# Grove_-_Laser_PM2_5_Sensor_HM3301.net
KiCad netlist of a schematic drawn in EAGLE
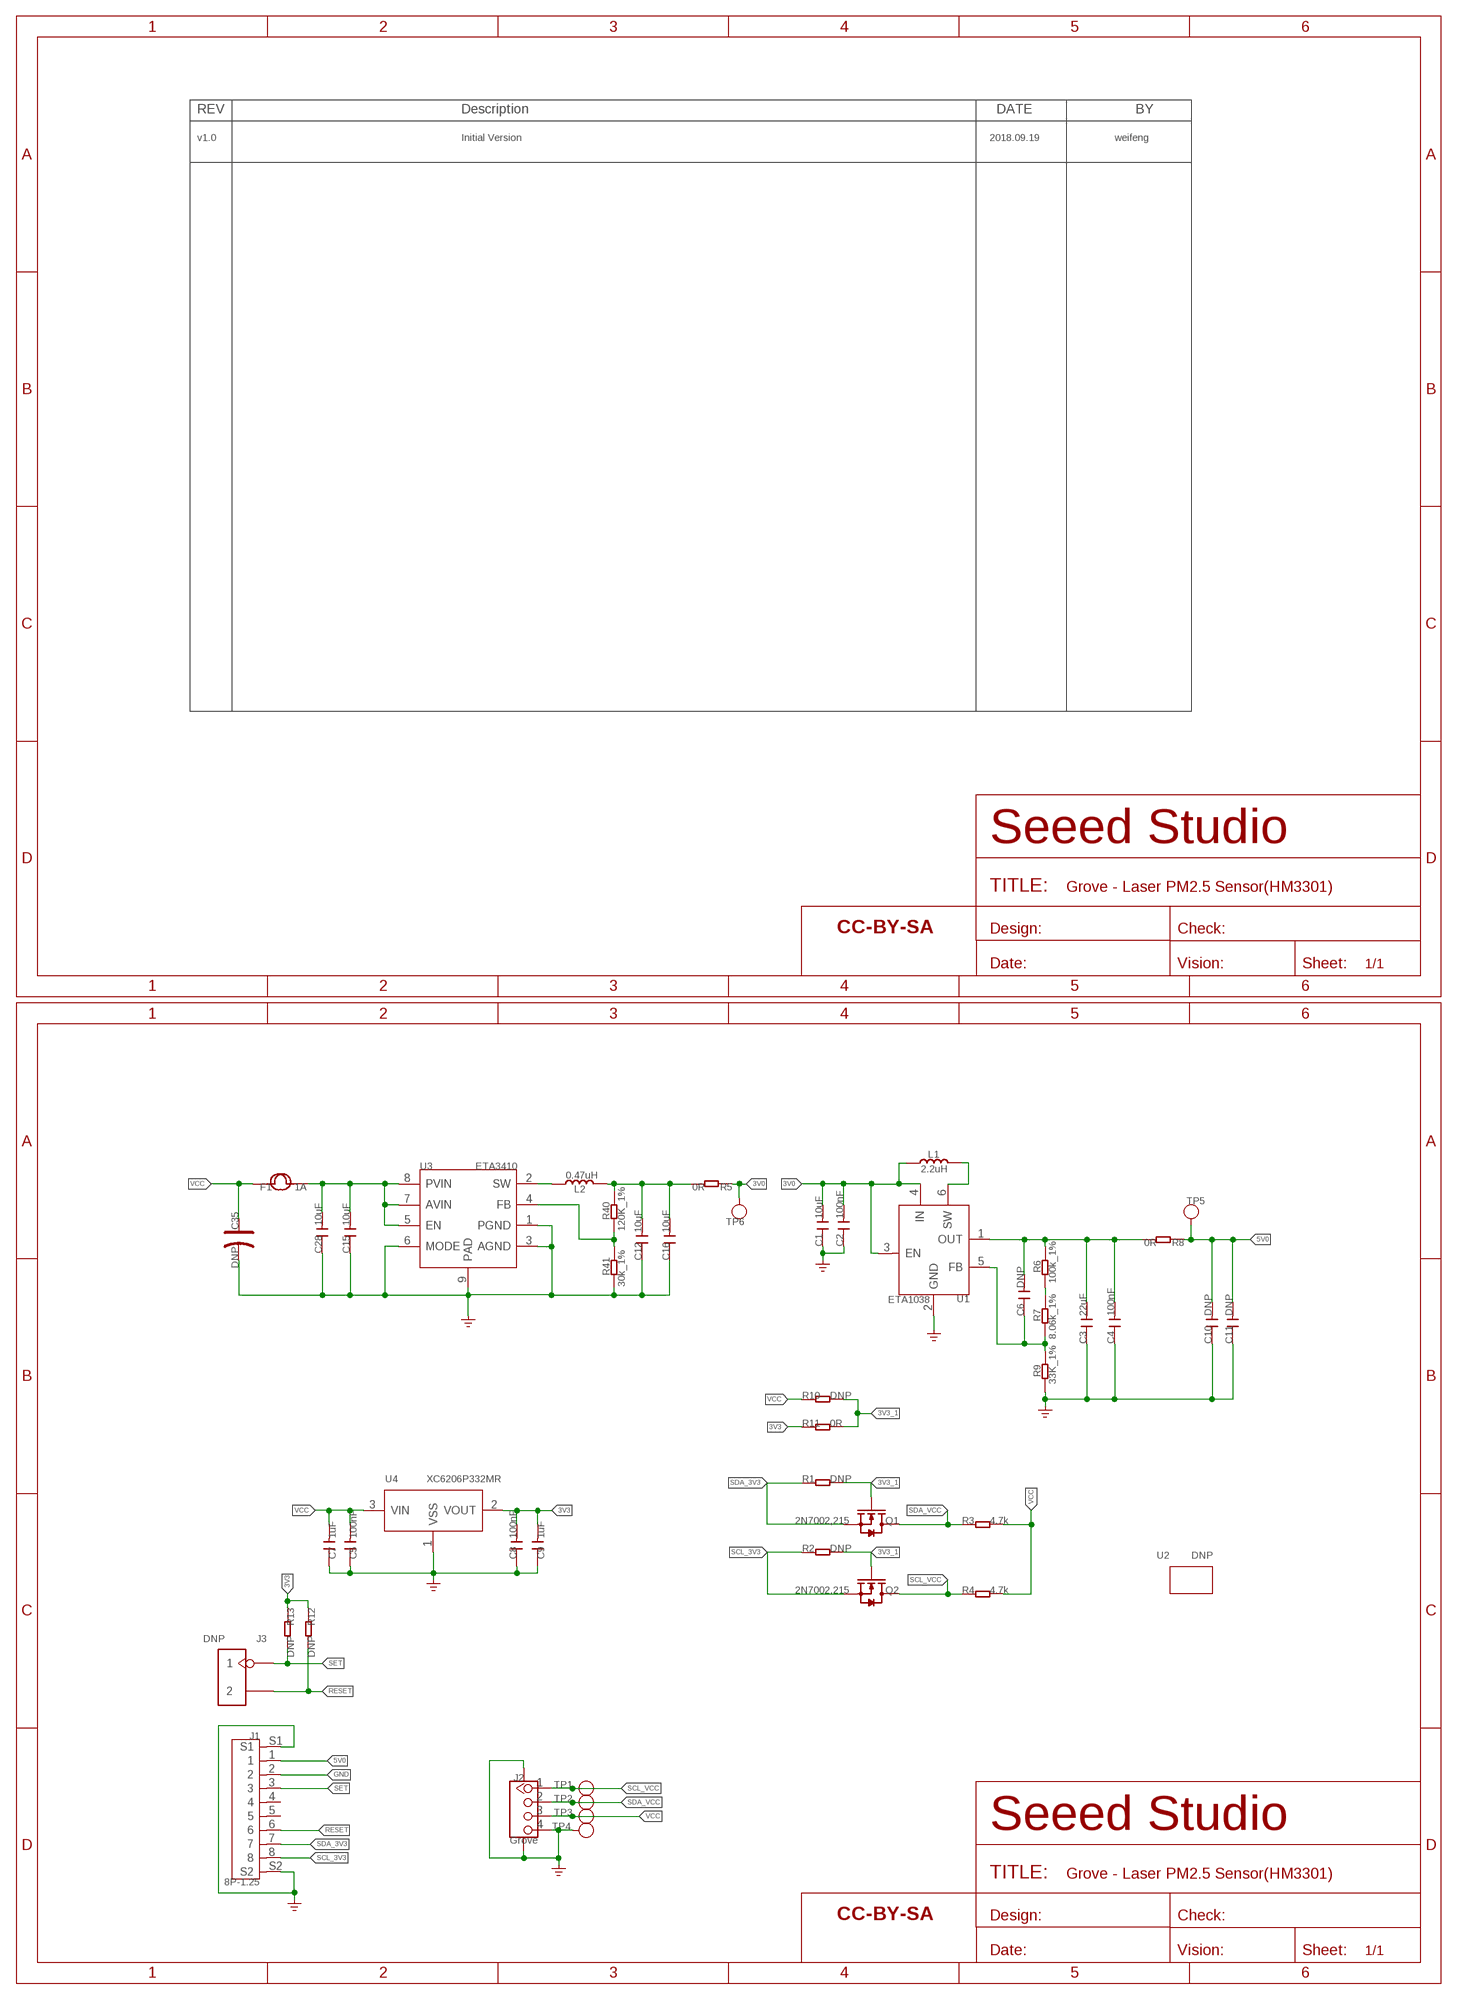
[diagram p0: schematic, sheet 1]

(export (version "E")
  (design (tool "Eeschema 10.0.6"))
  (components
    (comp (ref "C1")
      (value "10uF")
      (footprint "eagle-import:C0603")
      (libsource (lib "eagle-import") (part "C-0603"))
    )
    (comp (ref "C2")
      (value "100nF")
      (footprint "eagle-import:C0603")
      (libsource (lib "eagle-import") (part "C-0603"))
    )
    (comp (ref "C3")
      (value "22uF")
      (footprint "eagle-import:C0805")
      (libsource (lib "eagle-import") (part "C-0805"))
    )
    (comp (ref "C4")
      (value "100nF")
      (footprint "eagle-import:C0603")
      (libsource (lib "eagle-import") (part "C-0603"))
    )
    (comp (ref "C5")
      (value "100nF")
      (footprint "eagle-import:C0603")
      (libsource (lib "eagle-import") (part "C-0603"))
    )
    (comp (ref "C6")
      (value "DNP")
      (footprint "eagle-import:C0603")
      (libsource (lib "eagle-import") (part "C-0603"))
    )
    (comp (ref "C7")
      (value "1uF")
      (footprint "eagle-import:C0603")
      (libsource (lib "eagle-import") (part "C-0603"))
    )
    (comp (ref "C8")
      (value "100nF")
      (footprint "eagle-import:C0603")
      (libsource (lib "eagle-import") (part "C-0603"))
    )
    (comp (ref "C9")
      (value "1uF")
      (footprint "eagle-import:C0603")
      (libsource (lib "eagle-import") (part "C-0603"))
    )
    (comp (ref "C10")
      (value "DNP")
      (footprint "eagle-import:C0805")
      (libsource (lib "eagle-import") (part "C-0805"))
    )
    (comp (ref "C11")
      (value "DNP")
      (footprint "eagle-import:C0603")
      (libsource (lib "eagle-import") (part "C-0603"))
    )
    (comp (ref "C12")
      (value "10uF")
      (footprint "eagle-import:C0603")
      (libsource (lib "eagle-import") (part "C-0603"))
    )
    (comp (ref "C15")
      (value "10uF")
      (footprint "eagle-import:C0603")
      (libsource (lib "eagle-import") (part "C-0603"))
    )
    (comp (ref "C16")
      (value "10uF")
      (footprint "eagle-import:C0603")
      (libsource (lib "eagle-import") (part "C-0603"))
    )
    (comp (ref "C28")
      (value "10uF")
      (footprint "eagle-import:C0603")
      (libsource (lib "eagle-import") (part "C-0603"))
    )
    (comp (ref "C35")
      (value "DNP")
      (footprint "eagle-import:AVX-B")
      (libsource (lib "eagle-import") (part "CAP-POLAR-AVX-B"))
    )
    (comp (ref "F1")
      (value "1A")
      (footprint "eagle-import:F0805")
      (libsource (lib "eagle-import") (part "FUSE-0805"))
    )
    (comp (ref "FR1")
      (value "SEEEDSTUDIO-OPEN-SCH-FRAME")
      (footprint "eagle-import:SEEEDSTUDIO-PCB-FRAME")
      (libsource (lib "eagle-import") (part "SEEEDSTUDIO-OPEN-SCH-FRAME"))
    )
    (comp (ref "J1")
      (value "8P-1.25")
      (footprint "eagle-import:HEADER8+2P-SMD-1.25-15X3.5MM")
      (libsource (lib "eagle-import") (part "HEADER-8+2P"))
    )
    (comp (ref "J2")
      (value "Grove")
      (footprint "eagle-import:HW4-SMD-2.0-90D")
      (libsource (lib "eagle-import") (part "GROVE-CONNECTOR-SMD'90D'"))
    )
    (comp (ref "J3")
      (value "DNP")
      (footprint "eagle-import:H2-2.54")
      (libsource (lib "eagle-import") (part "HEADER-2P-65/35MIL"))
    )
    (comp (ref "L1")
      (value "2.2uH")
      (footprint "eagle-import:L0806")
      (libsource (lib "eagle-import") (part "INDUCTOR/FERRITE-BEAD'0806'"))
    )
    (comp (ref "L2")
      (value "0.47uH")
      (footprint "eagle-import:L201610")
      (libsource (lib "eagle-import") (part "L-MPM201610SR33_T"))
    )
    (comp (ref "Q1")
      (value "2N7002,215")
      (footprint "eagle-import:SOT-23")
      (libsource (lib "eagle-import") (part "MOSFET-N'SOT23'"))
    )
    (comp (ref "Q2")
      (value "2N7002,215")
      (footprint "eagle-import:SOT-23")
      (libsource (lib "eagle-import") (part "MOSFET-N'SOT23'"))
    )
    (comp (ref "R1")
      (value "DNP")
      (footprint "eagle-import:R0603")
      (libsource (lib "eagle-import") (part "R-0603"))
    )
    (comp (ref "R2")
      (value "DNP")
      (footprint "eagle-import:R0603")
      (libsource (lib "eagle-import") (part "R-0603"))
    )
    (comp (ref "R3")
      (value "4.7k")
      (footprint "eagle-import:R0603")
      (libsource (lib "eagle-import") (part "R-0603"))
    )
    (comp (ref "R4")
      (value "4.7k")
      (footprint "eagle-import:R0603")
      (libsource (lib "eagle-import") (part "R-0603"))
    )
    (comp (ref "R5")
      (value "0R")
      (footprint "eagle-import:R0603")
      (libsource (lib "eagle-import") (part "R-0603"))
    )
    (comp (ref "R6")
      (value "100k_1%")
      (footprint "eagle-import:R0603")
      (libsource (lib "eagle-import") (part "R-0603"))
    )
    (comp (ref "R7")
      (value "8.06k_1%")
      (footprint "eagle-import:R0603")
      (libsource (lib "eagle-import") (part "R-0603"))
    )
    (comp (ref "R8")
      (value "0R")
      (footprint "eagle-import:R0603")
      (libsource (lib "eagle-import") (part "R-0603"))
    )
    (comp (ref "R9")
      (value "33K_1%")
      (footprint "eagle-import:R0603")
      (libsource (lib "eagle-import") (part "R-0603"))
    )
    (comp (ref "R10")
      (value "DNP")
      (footprint "eagle-import:R0603")
      (libsource (lib "eagle-import") (part "R-0603"))
    )
    (comp (ref "R11")
      (value "0R")
      (footprint "eagle-import:R0603")
      (libsource (lib "eagle-import") (part "R-0603"))
    )
    (comp (ref "R12")
      (value "DNP")
      (footprint "eagle-import:R0603")
      (libsource (lib "eagle-import") (part "R-0603"))
    )
    (comp (ref "R13")
      (value "DNP")
      (footprint "eagle-import:R0603")
      (libsource (lib "eagle-import") (part "R-0603"))
    )
    (comp (ref "R40")
      (value "120K_1%")
      (footprint "eagle-import:R0603")
      (libsource (lib "eagle-import") (part "R-0603"))
    )
    (comp (ref "R41")
      (value "30k_1%")
      (footprint "eagle-import:R0603")
      (libsource (lib "eagle-import") (part "R-0603"))
    )
    (comp (ref "TP1")
      (value "TEST-POINT'4545'")
      (footprint "eagle-import:TP-D45MIL")
      (fields (field (name "PARTNO") "DNP"))
      (libsource (lib "eagle-import") (part "TEST-POINT'4545'"))
    )
    (comp (ref "TP2")
      (value "TEST-POINT'4545'")
      (footprint "eagle-import:TP-D45MIL")
      (fields (field (name "PARTNO") "DNP"))
      (libsource (lib "eagle-import") (part "TEST-POINT'4545'"))
    )
    (comp (ref "TP3")
      (value "TEST-POINT'4545'")
      (footprint "eagle-import:TP-D45MIL")
      (fields (field (name "PARTNO") "DNP"))
      (libsource (lib "eagle-import") (part "TEST-POINT'4545'"))
    )
    (comp (ref "TP4")
      (value "TEST-POINT'4545'")
      (footprint "eagle-import:TP-D45MIL")
      (fields (field (name "PARTNO") "DNP"))
      (libsource (lib "eagle-import") (part "TEST-POINT'4545'"))
    )
    (comp (ref "TP5")
      (value "TEST-POINT'4545'")
      (footprint "eagle-import:TP-D45MIL")
      (fields (field (name "PARTNO") "DNP"))
      (libsource (lib "eagle-import") (part "TEST-POINT'4545'"))
    )
    (comp (ref "TP6")
      (value "TEST-POINT'4545'")
      (footprint "eagle-import:TP-D45MIL")
      (fields (field (name "PARTNO") "DNP"))
      (libsource (lib "eagle-import") (part "TEST-POINT'4545'"))
    )
    (comp (ref "U$4")
      (value "SEEEDSTUDIO-OPEN-SCH-FRAME")
      (footprint "eagle-import:SEEEDSTUDIO-PCB-FRAME")
      (libsource (lib "eagle-import") (part "SEEEDSTUDIO-OPEN-SCH-FRAME"))
    )
    (comp (ref "U1")
      (value "ETA1038")
      (footprint "eagle-import:SOT-23-6")
      (libsource (lib "eagle-import") (part "CONVERTER-ETA1038"))
    )
    (comp (ref "U2")
      (value "DNP")
      (footprint "eagle-import:GROVE-80X40MM")
      (libsource (lib "eagle-import") (part "GROVE-80X40MM"))
    )
    (comp (ref "U3")
      (value "ETA3410")
      (footprint "eagle-import:DFN8G-0.5-2X2MM")
      (libsource (lib "eagle-import") (part "CONVERTER-ETA3410"))
    )
    (comp (ref "U4")
      (value "XC6206P332MR")
      (footprint "eagle-import:SOT-23")
      (libsource (lib "eagle-import") (part "PMIC-XC6206PMR"))
    )
  )
  (nets
    (net (code "1") (name "3V0") (class "Default")
      (node (ref "C1") (pin "2") (pinfunction "2_2") (pintype "passive"))
      (node (ref "C2") (pin "2") (pinfunction "2_2") (pintype "passive"))
      (node (ref "L1") (pin "1") (pinfunction "1_1") (pintype "passive"))
      (node (ref "R5") (pin "1") (pinfunction "1_1") (pintype "passive"))
      (node (ref "TP6") (pin "T") (pinfunction "T_T") (pintype "bidirectional"))
      (node (ref "U1") (pin "3") (pinfunction "EN_3") (pintype "bidirectional"))
      (node (ref "U1") (pin "4") (pinfunction "IN_4") (pintype "bidirectional"))
    )
    (net (code "2") (name "3V3") (class "Default")
      (node (ref "C8") (pin "2") (pinfunction "2_2") (pintype "passive"))
      (node (ref "C9") (pin "2") (pinfunction "2_2") (pintype "passive"))
      (node (ref "R11") (pin "1") (pinfunction "1_1") (pintype "passive"))
      (node (ref "R12") (pin "1") (pinfunction "1_1") (pintype "passive"))
      (node (ref "R13") (pin "1") (pinfunction "1_1") (pintype "passive"))
      (node (ref "U4") (pin "2") (pinfunction "VOUT_2") (pintype "bidirectional"))
    )
    (net (code "3") (name "3V3_1") (class "Default")
      (node (ref "Q1") (pin "1") (pinfunction "G_1") (pintype "passive"))
      (node (ref "Q2") (pin "1") (pinfunction "G_1") (pintype "passive"))
      (node (ref "R1") (pin "2") (pinfunction "2_2") (pintype "passive"))
      (node (ref "R10") (pin "2") (pinfunction "2_2") (pintype "passive"))
      (node (ref "R11") (pin "2") (pinfunction "2_2") (pintype "passive"))
      (node (ref "R2") (pin "2") (pinfunction "2_2") (pintype "passive"))
    )
    (net (code "4") (name "5V0") (class "Default")
      (node (ref "C10") (pin "2") (pinfunction "2_2") (pintype "passive"))
      (node (ref "C11") (pin "2") (pinfunction "2_2") (pintype "passive"))
      (node (ref "J1") (pin "1") (pinfunction "1_1") (pintype "bidirectional"))
      (node (ref "R8") (pin "1") (pinfunction "1_1") (pintype "passive"))
      (node (ref "TP5") (pin "T") (pinfunction "T_T") (pintype "bidirectional"))
    )
    (net (code "5") (name "GND") (class "Default")
      (node (ref "C1") (pin "1") (pinfunction "1_1") (pintype "passive"))
      (node (ref "C10") (pin "1") (pinfunction "1_1") (pintype "passive"))
      (node (ref "C11") (pin "1") (pinfunction "1_1") (pintype "passive"))
      (node (ref "C12") (pin "1") (pinfunction "1_1") (pintype "passive"))
      (node (ref "C15") (pin "1") (pinfunction "1_1") (pintype "passive"))
      (node (ref "C16") (pin "1") (pinfunction "1_1") (pintype "passive"))
      (node (ref "C2") (pin "1") (pinfunction "1_1") (pintype "passive"))
      (node (ref "C28") (pin "1") (pinfunction "1_1") (pintype "passive"))
      (node (ref "C3") (pin "1") (pinfunction "1_1") (pintype "passive"))
      (node (ref "C35") (pin "-") (pinfunction "-_-") (pintype "passive"))
      (node (ref "C4") (pin "1") (pinfunction "1_1") (pintype "passive"))
      (node (ref "C5") (pin "1") (pinfunction "1_1") (pintype "passive"))
      (node (ref "C7") (pin "1") (pinfunction "1_1") (pintype "passive"))
      (node (ref "C8") (pin "1") (pinfunction "1_1") (pintype "passive"))
      (node (ref "C9") (pin "1") (pinfunction "1_1") (pintype "passive"))
      (node (ref "J1") (pin "2") (pinfunction "2_2") (pintype "bidirectional"))
      (node (ref "J1") (pin "S1") (pinfunction "S1_S1") (pintype "bidirectional"))
      (node (ref "J1") (pin "S2") (pinfunction "S2_S2") (pintype "bidirectional"))
      (node (ref "J2") (pin "4") (pinfunction "4_4") (pintype "bidirectional"))
      (node (ref "J2") (pin "SS1") (pinfunction "SS1_SS1") (pintype "bidirectional"))
      (node (ref "J2") (pin "SS2") (pinfunction "SS2_SS2") (pintype "bidirectional"))
      (node (ref "R41") (pin "1") (pinfunction "1_1") (pintype "passive"))
      (node (ref "R9") (pin "2") (pinfunction "2_2") (pintype "passive"))
      (node (ref "TP4") (pin "T") (pinfunction "T_T") (pintype "bidirectional"))
      (node (ref "U1") (pin "2") (pinfunction "GND_2") (pintype "bidirectional"))
      (node (ref "U3") (pin "1") (pinfunction "PGND_1") (pintype "bidirectional"))
      (node (ref "U3") (pin "3") (pinfunction "AGND_3") (pintype "bidirectional"))
      (node (ref "U3") (pin "6") (pinfunction "MODE_6") (pintype "bidirectional"))
      (node (ref "U3") (pin "9") (pinfunction "PAD_9") (pintype "bidirectional"))
      (node (ref "U4") (pin "1") (pinfunction "VSS_1") (pintype "bidirectional"))
    )
    (net (code "6") (name "Net-(C12-Pad2)") (class "Default")
      (node (ref "C12") (pin "2") (pinfunction "2_2") (pintype "passive"))
      (node (ref "C16") (pin "2") (pinfunction "2_2") (pintype "passive"))
      (node (ref "L2") (pin "2") (pinfunction "2_2") (pintype "passive"))
      (node (ref "R40") (pin "2") (pinfunction "2_2") (pintype "passive"))
      (node (ref "R5") (pin "2") (pinfunction "2_2") (pintype "passive"))
    )
    (net (code "7") (name "Net-(R6-Pad2)") (class "Default")
      (node (ref "R6") (pin "2") (pinfunction "2_2") (pintype "passive"))
      (node (ref "R7") (pin "1") (pinfunction "1_1") (pintype "passive"))
    )
    (net (code "8") (name "Net-(U1-FB)") (class "Default")
      (node (ref "C6") (pin "1") (pinfunction "1_1") (pintype "passive"))
      (node (ref "R7") (pin "2") (pinfunction "2_2") (pintype "passive"))
      (node (ref "R9") (pin "1") (pinfunction "1_1") (pintype "passive"))
      (node (ref "U1") (pin "5") (pinfunction "FB_5") (pintype "bidirectional"))
    )
    (net (code "9") (name "Net-(U1-OUT)") (class "Default")
      (node (ref "C3") (pin "2") (pinfunction "2_2") (pintype "passive"))
      (node (ref "C4") (pin "2") (pinfunction "2_2") (pintype "passive"))
      (node (ref "C6") (pin "2") (pinfunction "2_2") (pintype "passive"))
      (node (ref "R6") (pin "1") (pinfunction "1_1") (pintype "passive"))
      (node (ref "R8") (pin "2") (pinfunction "2_2") (pintype "passive"))
      (node (ref "U1") (pin "1") (pinfunction "OUT_1") (pintype "bidirectional"))
    )
    (net (code "10") (name "Net-(U1-SW)") (class "Default")
      (node (ref "L1") (pin "2") (pinfunction "2_2") (pintype "passive"))
      (node (ref "U1") (pin "6") (pinfunction "SW_6") (pintype "bidirectional"))
    )
    (net (code "11") (name "Net-(U3-AVIN)") (class "Default")
      (node (ref "C15") (pin "2") (pinfunction "2_2") (pintype "passive"))
      (node (ref "C28") (pin "2") (pinfunction "2_2") (pintype "passive"))
      (node (ref "F1") (pin "2") (pinfunction "2_2") (pintype "bidirectional"))
      (node (ref "U3") (pin "5") (pinfunction "EN_5") (pintype "bidirectional"))
      (node (ref "U3") (pin "7") (pinfunction "AVIN_7") (pintype "bidirectional"))
      (node (ref "U3") (pin "8") (pinfunction "PVIN_8") (pintype "bidirectional"))
    )
    (net (code "12") (name "Net-(U3-FB)") (class "Default")
      (node (ref "R40") (pin "1") (pinfunction "1_1") (pintype "passive"))
      (node (ref "R41") (pin "2") (pinfunction "2_2") (pintype "passive"))
      (node (ref "U3") (pin "4") (pinfunction "FB_4") (pintype "bidirectional"))
    )
    (net (code "13") (name "Net-(U3-SW)") (class "Default")
      (node (ref "L2") (pin "1") (pinfunction "1_1") (pintype "passive"))
      (node (ref "U3") (pin "2") (pinfunction "SW_2") (pintype "bidirectional"))
    )
    (net (code "14") (name "RESET") (class "Default")
      (node (ref "J1") (pin "6") (pinfunction "6_6") (pintype "bidirectional"))
      (node (ref "J3") (pin "2") (pinfunction "2_2") (pintype "bidirectional"))
      (node (ref "R12") (pin "2") (pinfunction "2_2") (pintype "passive"))
    )
    (net (code "15") (name "SCL_3V3") (class "Default")
      (node (ref "J1") (pin "8") (pinfunction "8_8") (pintype "bidirectional"))
      (node (ref "Q2") (pin "2") (pinfunction "S_2") (pintype "passive"))
      (node (ref "R2") (pin "1") (pinfunction "1_1") (pintype "passive"))
    )
    (net (code "16") (name "SCL_VCC") (class "Default")
      (node (ref "J2") (pin "1") (pinfunction "1_1") (pintype "bidirectional"))
      (node (ref "Q2") (pin "3") (pinfunction "D_3") (pintype "passive"))
      (node (ref "R4") (pin "1") (pinfunction "1_1") (pintype "passive"))
      (node (ref "TP1") (pin "T") (pinfunction "T_T") (pintype "bidirectional"))
    )
    (net (code "17") (name "SDA_3V3") (class "Default")
      (node (ref "J1") (pin "7") (pinfunction "7_7") (pintype "bidirectional"))
      (node (ref "Q1") (pin "2") (pinfunction "S_2") (pintype "passive"))
      (node (ref "R1") (pin "1") (pinfunction "1_1") (pintype "passive"))
    )
    (net (code "18") (name "SDA_VCC") (class "Default")
      (node (ref "J2") (pin "2") (pinfunction "2_2") (pintype "bidirectional"))
      (node (ref "Q1") (pin "3") (pinfunction "D_3") (pintype "passive"))
      (node (ref "R3") (pin "1") (pinfunction "1_1") (pintype "passive"))
      (node (ref "TP2") (pin "T") (pinfunction "T_T") (pintype "bidirectional"))
    )
    (net (code "19") (name "SET") (class "Default")
      (node (ref "J1") (pin "3") (pinfunction "3_3") (pintype "bidirectional"))
      (node (ref "J3") (pin "1") (pinfunction "1_1") (pintype "bidirectional"))
      (node (ref "R13") (pin "2") (pinfunction "2_2") (pintype "passive"))
    )
    (net (code "20") (name "VCC") (class "Default")
      (node (ref "C35") (pin "+") (pinfunction "+_+") (pintype "passive"))
      (node (ref "C5") (pin "2") (pinfunction "2_2") (pintype "passive"))
      (node (ref "C7") (pin "2") (pinfunction "2_2") (pintype "passive"))
      (node (ref "F1") (pin "1") (pinfunction "1_1") (pintype "bidirectional"))
      (node (ref "J2") (pin "3") (pinfunction "3_3") (pintype "bidirectional"))
      (node (ref "R10") (pin "1") (pinfunction "1_1") (pintype "passive"))
      (node (ref "R3") (pin "2") (pinfunction "2_2") (pintype "passive"))
      (node (ref "R4") (pin "2") (pinfunction "2_2") (pintype "passive"))
      (node (ref "TP3") (pin "T") (pinfunction "T_T") (pintype "bidirectional"))
      (node (ref "U4") (pin "3") (pinfunction "VIN_3") (pintype "bidirectional"))
    )
    (net (code "21") (name "unconnected-(J1-Pad4)") (class "Default")
      (node (ref "J1") (pin "4") (pinfunction "4_4") (pintype "bidirectional"))
    )
    (net (code "22") (name "unconnected-(J1-Pad5)") (class "Default")
      (node (ref "J1") (pin "5") (pinfunction "5_5") (pintype "bidirectional"))
    )
  )
)
